# MP9929-BUCK.net
KiCad netlist of a schematic drawn in EasyEDA Pro
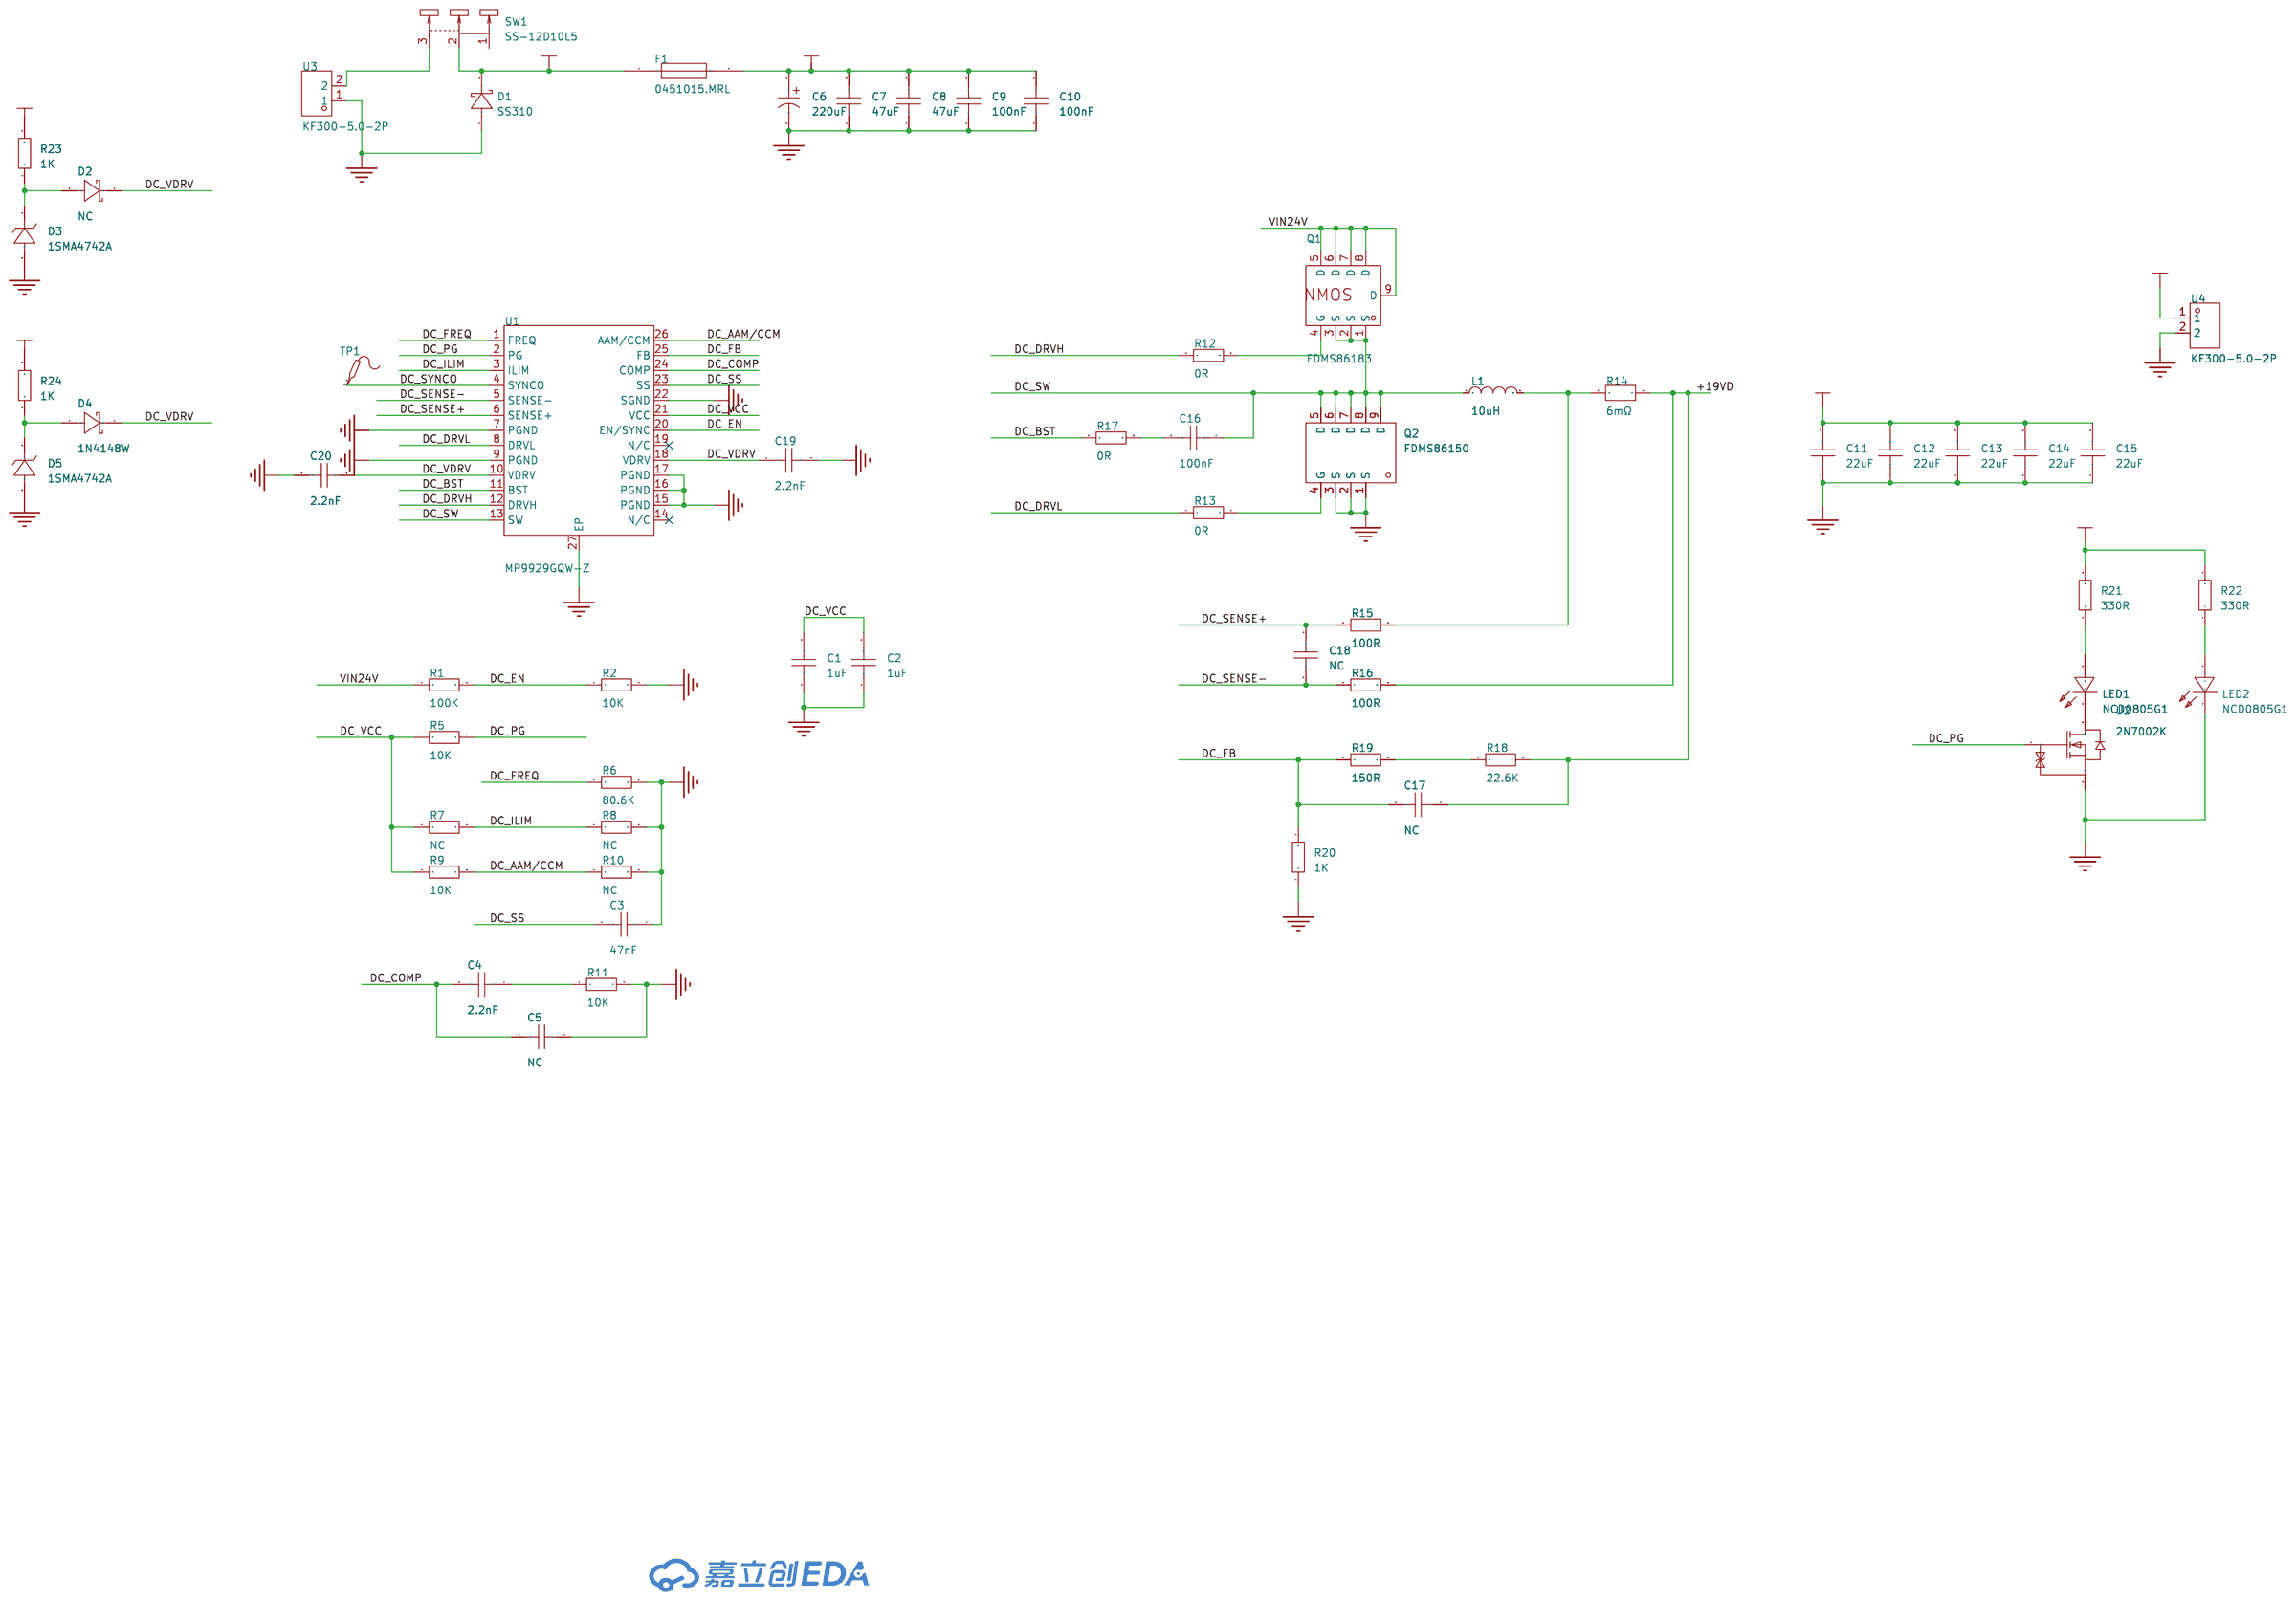
[diagram p0: schematic sheet]

(export (version "E")
  (design (tool "Eeschema 10.0.6"))
  (components
    (comp (ref "C1")
      (value "1uF")
      (footprint "easyedapro:C0603")
      (libsource (lib "easyedapro") (part "Capacitance"))
    )
    (comp (ref "C2")
      (value "1uF")
      (footprint "easyedapro:C0603")
      (libsource (lib "easyedapro") (part "Capacitance"))
    )
    (comp (ref "C3")
      (value "47nF")
      (footprint "easyedapro:C0603")
      (libsource (lib "easyedapro") (part "Capacitance"))
    )
    (comp (ref "C4")
      (value "2.2nF")
      (footprint "easyedapro:C0603")
      (libsource (lib "easyedapro") (part "Capacitance"))
    )
    (comp (ref "C5")
      (value "NC")
      (footprint "easyedapro:C0603")
      (libsource (lib "easyedapro") (part "Capacitance"))
    )
    (comp (ref "C6")
      (value "220uF")
      (footprint "easyedapro:CAP-SMD_BD10.0-L10.3-W10.3-LS11.7-FD")
      (description "容值:220uF;精度:±20%;额定电压:50V;纹波电流:220mA@120Hz;")
      (fields (field (name "Manufacturer Part") "JVJ50V220M10x10") (field (name "Manufacturer") "JIERR(捷而瑞)"))
      (libsource (lib "easyedapro") (part "JVJ50V220M10X10"))
    )
    (comp (ref "C7")
      (value "47uF")
      (footprint "easyedapro:C1210")
      (description "容值:47uF;精度:±20%;额定电压:25V;温度系数:X5R;")
      (fields
        (field (name "Manufacturer Part") "HGC1210R5476M250NSVK")
        (field (name "Manufacturer") "Chinocera(华瓷)")
      )
      (libsource (lib "easyedapro") (part "HGC1210R5476M250NSVK"))
    )
    (comp (ref "C8")
      (value "47uF")
      (footprint "easyedapro:C1210")
      (description "容值:47uF;精度:±20%;额定电压:25V;温度系数:X5R;")
      (fields
        (field (name "Manufacturer Part") "HGC1210R5476M250NSVK")
        (field (name "Manufacturer") "Chinocera(华瓷)")
      )
      (libsource (lib "easyedapro") (part "HGC1210R5476M250NSVK"))
    )
    (comp (ref "C9")
      (value "100nF")
      (footprint "easyedapro:C0603")
      (description "容值:100nF;精度:±10%;额定电压:50V;温度系数:X7R;")
      (fields
        (field (name "Manufacturer Part") "CL10B104KB8NNNC")
        (field (name "Manufacturer") "SAMSUNG(三星)")
      )
      (libsource (lib "easyedapro") (part "CL10B104KB8NNNC"))
    )
    (comp (ref "C10")
      (value "100nF")
      (footprint "easyedapro:C0603")
      (description "容值:100nF;精度:±10%;额定电压:50V;温度系数:X7R;")
      (fields
        (field (name "Manufacturer Part") "CL10B104KB8NNNC")
        (field (name "Manufacturer") "SAMSUNG(三星)")
      )
      (libsource (lib "easyedapro") (part "CL10B104KB8NNNC"))
    )
    (comp (ref "C11")
      (value "22uF")
      (footprint "easyedapro:C1210")
      (description "容值:47uF;精度:±20%;额定电压:25V;温度系数:X5R;")
      (fields
        (field (name "Manufacturer Part") "HGC1210R5476M250NSVK")
        (field (name "Manufacturer") "Chinocera(华瓷)")
      )
      (libsource (lib "easyedapro") (part "HGC1210R5476M250NSVK"))
    )
    (comp (ref "C12")
      (value "22uF")
      (footprint "easyedapro:C1210")
      (description "容值:47uF;精度:±20%;额定电压:25V;温度系数:X5R;")
      (fields
        (field (name "Manufacturer Part") "HGC1210R5476M250NSVK")
        (field (name "Manufacturer") "Chinocera(华瓷)")
      )
      (libsource (lib "easyedapro") (part "HGC1210R5476M250NSVK"))
    )
    (comp (ref "C13")
      (value "22uF")
      (footprint "easyedapro:C1210")
      (description "容值:47uF;精度:±20%;额定电压:25V;温度系数:X5R;")
      (fields
        (field (name "Manufacturer Part") "HGC1210R5476M250NSVK")
        (field (name "Manufacturer") "Chinocera(华瓷)")
      )
      (libsource (lib "easyedapro") (part "HGC1210R5476M250NSVK"))
    )
    (comp (ref "C14")
      (value "22uF")
      (footprint "easyedapro:C1210")
      (description "容值:47uF;精度:±20%;额定电压:25V;温度系数:X5R;")
      (fields
        (field (name "Manufacturer Part") "HGC1210R5476M250NSVK")
        (field (name "Manufacturer") "Chinocera(华瓷)")
      )
      (libsource (lib "easyedapro") (part "HGC1210R5476M250NSVK"))
    )
    (comp (ref "C15")
      (value "22uF")
      (footprint "easyedapro:C1210")
      (description "容值:47uF;精度:±20%;额定电压:25V;温度系数:X5R;")
      (fields
        (field (name "Manufacturer Part") "HGC1210R5476M250NSVK")
        (field (name "Manufacturer") "Chinocera(华瓷)")
      )
      (libsource (lib "easyedapro") (part "HGC1210R5476M250NSVK"))
    )
    (comp (ref "C16")
      (value "100nF")
      (footprint "easyedapro:C0603")
      (description "容值:100nF;精度:±10%;额定电压:50V;温度系数:X7R;")
      (fields
        (field (name "Manufacturer Part") "CL10B104KB8NNNC")
        (field (name "Manufacturer") "SAMSUNG(三星)")
      )
      (libsource (lib "easyedapro") (part "CL10B104KB8NNNC"))
    )
    (comp (ref "C17")
      (value "NC")
      (footprint "easyedapro:C0603")
      (libsource (lib "easyedapro") (part "Capacitance"))
    )
    (comp (ref "C18")
      (value "NC")
      (footprint "easyedapro:C0603")
      (description "容值:100nF;精度:±10%;额定电压:50V;温度系数:X7R;")
      (fields
        (field (name "Manufacturer Part") "CL10B104KB8NNNC")
        (field (name "Manufacturer") "SAMSUNG(三星)")
      )
      (libsource (lib "easyedapro") (part "CL10B104KB8NNNC"))
    )
    (comp (ref "C19")
      (value "2.2nF")
      (footprint "easyedapro:C0603")
      (libsource (lib "easyedapro") (part "Capacitance"))
    )
    (comp (ref "C20")
      (value "2.2nF")
      (footprint "easyedapro:C0603")
      (libsource (lib "easyedapro") (part "Capacitance"))
    )
    (comp (ref "D1")
      (value "SS310")
      (footprint "easyedapro:SMA_L4.3-W2.6-LS5.0-FD")
      (description "二极管配置:独立式;正向压降(Vf):850mV@3A;直流反向耐压(Vr):100V;整流电流:3A;")
      (fields (field (name "Manufacturer") "R+O(宏嘉诚)"))
      (libsource (lib "easyedapro") (part "SS310_C7420364"))
    )
    (comp (ref "D2")
      (value "NC")
      (footprint "easyedapro:SOD-123_L2.7-W1.6-LS3.7-FD")
      (description "二极管配置:独立式;正向压降(Vf):1.25V@150mA;直流反向耐压(Vr):100V;整流电流:150mA;反向恢复时间(Trr):4ns;")
      (fields (field (name "Manufacturer") "R+O(宏嘉诚)"))
      (libsource (lib "easyedapro") (part "1N4148W_C7420318"))
    )
    (comp (ref "D3")
      (value "1SMA4742A")
      (footprint "easyedapro:SMA_L4.3-W2.6-LS5.0-RD")
      (description "二极管配置:独立式;稳压值(标称值):12V;稳压值(范围):11.4V~12.6V;耗散功率(Pd):1W;")
      (fields (field (name "Manufacturer") "R+O(宏嘉诚)"))
      (libsource (lib "easyedapro") (part "1SMA4742A_C19077480"))
    )
    (comp (ref "D4")
      (value "1N4148W")
      (footprint "easyedapro:SOD-123_L2.7-W1.6-LS3.7-FD")
      (description "二极管配置:独立式;正向压降(Vf):1.25V@150mA;直流反向耐压(Vr):100V;整流电流:150mA;反向恢复时间(Trr):4ns;")
      (fields (field (name "Manufacturer") "R+O(宏嘉诚)"))
      (libsource (lib "easyedapro") (part "1N4148W_C7420318"))
    )
    (comp (ref "D5")
      (value "1SMA4742A")
      (footprint "easyedapro:SMA_L4.3-W2.6-LS5.0-RD")
      (description "二极管配置:独立式;稳压值(标称值):12V;稳压值(范围):11.4V~12.6V;耗散功率(Pd):1W;")
      (fields (field (name "Manufacturer") "R+O(宏嘉诚)"))
      (libsource (lib "easyedapro") (part "1SMA4742A_C19077480"))
    )
    (comp (ref "F1")
      (value "0451015.MRL")
      (footprint "easyedapro:FUSE-SMD_L6.1-W2.6")
      (description "类型:贴片式保险丝;额定电流:15A;额定电压 (AC):65V;额定电压:65V;分断能力:50A;")
      (fields (field (name "Manufacturer") "Littelfuse(美国力特)"))
      (libsource (lib "easyedapro") (part "0451015.MRL"))
    )
    (comp (ref "L1")
      (value "10uH")
      (footprint "easyedapro:IND-SMD_L11.5-W10.0_FXL1040")
      (description "电感值:10uH;精度:±20%;额定电流:7.8A;饱和电流(Isat):8.5A;类型:一体成型电感;")
      (fields (field (name "Manufacturer Part") "FXL1040-100-M") (field (name "Manufacturer") "cjiang(长江微电)"))
      (libsource (lib "easyedapro") (part "FXL1040-100-M"))
    )
    (comp (ref "LED1")
      (value "NCD0805G1")
      (footprint "easyedapro:LED0805-R-RD")
      (fields (field (name "Manufacturer") "国星光电"))
      (libsource (lib "easyedapro") (part "FC-2012UGK-520D5"))
    )
    (comp (ref "LED2")
      (value "NCD0805G1")
      (footprint "easyedapro:LED0805-R-RD")
      (fields (field (name "Manufacturer") "国星光电"))
      (libsource (lib "easyedapro") (part "FC-2012UGK-520D5"))
    )
    (comp (ref "Q1")
      (value "FDMS86183")
      (footprint "easyedapro:POWER-56_L5.0-W6.0-P1.27-LS6.2-BL")
      (description "类型:-;漏源电压(Vdss):-;连续漏极电流(Id):-;功率(Pd):-;导通电阻(RDS(on)@Vgs,Id):-;阈值电压(Vgs(th)@Id):-;")
      (fields (field (name "Manufacturer") "onsemi(安森美)"))
      (libsource (lib "easyedapro") (part "FDMS86183"))
    )
    (comp (ref "Q2")
      (value "FDMS86150")
      (footprint "easyedapro:POWER-56_L5.0-W6.0-P1.27-LS6.2-BL")
      (description "数量:1个N沟道;漏源电压(Vdss):100V;连续漏极电流(Id):80A;导通电阻(RDS(on)):7.8mΩ@6V,13A;耗散功率(Pd):156W;阈值电压(Vgs(th)):2V;")
      (fields (field (name "Manufacturer") "onsemi(安森美)"))
      (libsource (lib "easyedapro") (part "FDMS86150"))
    )
    (comp (ref "R1") (value "100K") (footprint "easyedapro:R0603") (libsource (lib "easyedapro") (part "电阻")))
    (comp (ref "R2") (value "10K") (footprint "easyedapro:R0603") (libsource (lib "easyedapro") (part "电阻")))
    (comp (ref "R5") (value "10K") (footprint "easyedapro:R0603") (libsource (lib "easyedapro") (part "电阻")))
    (comp (ref "R6")
      (value "80.6K")
      (footprint "easyedapro:R0603")
      (libsource (lib "easyedapro") (part "电阻"))
    )
    (comp (ref "R7") (value "NC") (footprint "easyedapro:R0603") (libsource (lib "easyedapro") (part "电阻")))
    (comp (ref "R8") (value "NC") (footprint "easyedapro:R0603") (libsource (lib "easyedapro") (part "电阻")))
    (comp (ref "R9") (value "10K") (footprint "easyedapro:R0603") (libsource (lib "easyedapro") (part "电阻")))
    (comp (ref "R10") (value "NC") (footprint "easyedapro:R0603") (libsource (lib "easyedapro") (part "电阻")))
    (comp (ref "R11") (value "10K") (footprint "easyedapro:R0603") (libsource (lib "easyedapro") (part "电阻")))
    (comp (ref "R12") (value "0R") (footprint "easyedapro:R0603") (libsource (lib "easyedapro") (part "电阻")))
    (comp (ref "R13") (value "0R") (footprint "easyedapro:R0603") (libsource (lib "easyedapro") (part "电阻")))
    (comp (ref "R14")
      (value "6mΩ")
      (footprint "easyedapro:RES-SMD_L6.4-W3.2-R2512")
      (description "电阻类型:采样电阻；合金电阻;阻值:6mΩ;精度:±1%;功率:3W;温度系数:±100ppm/°C;")
      (fields (field (name "Manufacturer Part") "RE2512F3R006") (field (name "Manufacturer") "JIERR(捷而瑞)"))
      (libsource (lib "easyedapro") (part "RE2512F3R006"))
    )
    (comp (ref "R15")
      (value "100R")
      (footprint "easyedapro:R0603")
      (libsource (lib "easyedapro") (part "电阻"))
    )
    (comp (ref "R16")
      (value "100R")
      (footprint "easyedapro:R0603")
      (libsource (lib "easyedapro") (part "电阻"))
    )
    (comp (ref "R17") (value "0R") (footprint "easyedapro:R0603") (libsource (lib "easyedapro") (part "电阻")))
    (comp (ref "R18")
      (value "22.6K")
      (footprint "easyedapro:R0603")
      (libsource (lib "easyedapro") (part "电阻"))
    )
    (comp (ref "R19")
      (value "150R")
      (footprint "easyedapro:R0603")
      (libsource (lib "easyedapro") (part "电阻"))
    )
    (comp (ref "R20") (value "1K") (footprint "easyedapro:R0603") (libsource (lib "easyedapro") (part "电阻")))
    (comp (ref "R21")
      (value "330R")
      (footprint "easyedapro:R0603")
      (libsource (lib "easyedapro") (part "电阻"))
    )
    (comp (ref "R22")
      (value "330R")
      (footprint "easyedapro:R0603")
      (libsource (lib "easyedapro") (part "电阻"))
    )
    (comp (ref "R23") (value "1K") (footprint "easyedapro:R0603") (libsource (lib "easyedapro") (part "电阻")))
    (comp (ref "R24") (value "1K") (footprint "easyedapro:R0603") (libsource (lib "easyedapro") (part "电阻")))
    (comp (ref "SW1")
      (value "SS-12D10L5")
      (footprint "easyedapro:SW-TH_SS-12D10L5")
      (description "电路结构:单刀双掷;安装方式:直插;开关颜色:黑色;额定电流:3A;额定电压:125V;工作寿命:1万次;")
      (fields (field (name "Manufacturer") "XKB Connection(中国星坤)"))
      (libsource (lib "easyedapro") (part "SS-12D10L5"))
    )
    (comp (ref "TP1")
      (value "~")
      (footprint "easyedapro:Test-Point-0.5mm")
      (description "Test Point 测试点")
      (libsource (lib "easyedapro") (part "Test-Point"))
    )
    (comp (ref "U1")
      (value "MP9929GQW-Z")
      (footprint "easyedapro:QFN-26_L6.0-W4.0-P0.50_MP9929GQW-Z")
      (fields (field (name "Manufacturer") "MPS(芯源)"))
      (libsource (lib "easyedapro") (part "MP9929GQW-Z"))
    )
    (comp (ref "U2")
      (value "2N7002K")
      (footprint "easyedapro:SOT-23-3_L2.9-W1.3-P0.95-LS2.4-BR")
      (fields (field (name "Manufacturer") "R+O(宏嘉诚)"))
      (libsource (lib "easyedapro") (part "2N7002K_C22379475"))
    )
    (comp (ref "U3")
      (value "KF300-5.0-2P")
      (footprint "easyedapro:CONN-TH_P5.00_KF300-5.0-2P")
      (fields (field (name "Manufacturer") "KEFA(科发)"))
      (libsource (lib "easyedapro") (part "KF300-5.0-2P"))
    )
    (comp (ref "U4")
      (value "KF300-5.0-2P")
      (footprint "easyedapro:CONN-TH_P5.00_KF300-5.0-2P")
      (fields (field (name "Manufacturer") "KEFA(科发)"))
      (libsource (lib "easyedapro") (part "KF300-5.0-2P"))
    )
  )
  (nets
    (net (code "1") (name "+19VD") (class "Default")
      (node (ref "C11") (pin "2") (pinfunction "2_2") (pintype "unspecified"))
      (node (ref "C12") (pin "2") (pinfunction "2_2") (pintype "unspecified"))
      (node (ref "C13") (pin "2") (pinfunction "2_2") (pintype "unspecified"))
      (node (ref "C14") (pin "2") (pinfunction "2_2") (pintype "unspecified"))
      (node (ref "C15") (pin "2") (pinfunction "2_2") (pintype "unspecified"))
      (node (ref "C17") (pin "1") (pinfunction "1_1") (pintype "input"))
      (node (ref "R14") (pin "2") (pinfunction "2_2") (pintype "unspecified"))
      (node (ref "R16") (pin "2") (pinfunction "2_2") (pintype "input"))
      (node (ref "R18") (pin "2") (pinfunction "2_2") (pintype "input"))
      (node (ref "R21") (pin "2") (pinfunction "2_2") (pintype "input"))
      (node (ref "R22") (pin "2") (pinfunction "2_2") (pintype "input"))
      (node (ref "R23") (pin "2") (pinfunction "2_2") (pintype "input"))
      (node (ref "U4") (pin "1") (pinfunction "1_1") (pintype "unspecified"))
    )
    (net (code "2") (name "/DC_AAM{slash}CCM") (class "Default")
      (node (ref "R10") (pin "1") (pinfunction "1_1") (pintype "input"))
      (node (ref "R9") (pin "2") (pinfunction "2_2") (pintype "input"))
      (node (ref "U1") (pin "26") (pinfunction "AAM/CCM_26") (pintype "unspecified"))
    )
    (net (code "3") (name "/DC_BST") (class "Default")
      (node (ref "R17") (pin "1") (pinfunction "1_1") (pintype "input"))
      (node (ref "U1") (pin "11") (pinfunction "BST_11") (pintype "unspecified"))
    )
    (net (code "4") (name "/DC_COMP") (class "Default")
      (node (ref "C4") (pin "2") (pinfunction "2_2") (pintype "input"))
      (node (ref "C5") (pin "2") (pinfunction "2_2") (pintype "input"))
      (node (ref "U1") (pin "24") (pinfunction "COMP_24") (pintype "unspecified"))
    )
    (net (code "5") (name "/DC_DRVH") (class "Default")
      (node (ref "R12") (pin "1") (pinfunction "1_1") (pintype "input"))
      (node (ref "U1") (pin "12") (pinfunction "DRVH_12") (pintype "unspecified"))
    )
    (net (code "6") (name "/DC_DRVL") (class "Default")
      (node (ref "R13") (pin "1") (pinfunction "1_1") (pintype "input"))
      (node (ref "U1") (pin "8") (pinfunction "DRVL_8") (pintype "unspecified"))
    )
    (net (code "7") (name "/DC_EN") (class "Default")
      (node (ref "R1") (pin "2") (pinfunction "2_2") (pintype "input"))
      (node (ref "R2") (pin "1") (pinfunction "1_1") (pintype "input"))
      (node (ref "U1") (pin "20") (pinfunction "EN/SYNC_20") (pintype "unspecified"))
    )
    (net (code "8") (name "/DC_FB") (class "Default")
      (node (ref "C17") (pin "2") (pinfunction "2_2") (pintype "input"))
      (node (ref "R19") (pin "1") (pinfunction "1_1") (pintype "input"))
      (node (ref "R20") (pin "2") (pinfunction "2_2") (pintype "input"))
      (node (ref "U1") (pin "25") (pinfunction "FB_25") (pintype "unspecified"))
    )
    (net (code "9") (name "/DC_FREQ") (class "Default")
      (node (ref "R6") (pin "1") (pinfunction "1_1") (pintype "input"))
      (node (ref "U1") (pin "1") (pinfunction "FREQ_1") (pintype "unspecified"))
    )
    (net (code "10") (name "/DC_ILIM") (class "Default")
      (node (ref "R7") (pin "2") (pinfunction "2_2") (pintype "input"))
      (node (ref "R8") (pin "1") (pinfunction "1_1") (pintype "input"))
      (node (ref "U1") (pin "3") (pinfunction "ILIM_3") (pintype "unspecified"))
    )
    (net (code "11") (name "/DC_PG") (class "Default")
      (node (ref "R5") (pin "2") (pinfunction "2_2") (pintype "input"))
      (node (ref "U1") (pin "2") (pinfunction "PG_2") (pintype "unspecified"))
      (node (ref "U2") (pin "1") (pinfunction "G_1") (pintype "unspecified"))
    )
    (net (code "12") (name "/DC_SENSE+") (class "Default")
      (node (ref "C18") (pin "1") (pinfunction "1_1") (pintype "unspecified"))
      (node (ref "R15") (pin "1") (pinfunction "1_1") (pintype "input"))
      (node (ref "U1") (pin "6") (pinfunction "SENSE+_6") (pintype "unspecified"))
    )
    (net (code "13") (name "/DC_SENSE-") (class "Default")
      (node (ref "C18") (pin "2") (pinfunction "2_2") (pintype "unspecified"))
      (node (ref "R16") (pin "1") (pinfunction "1_1") (pintype "input"))
      (node (ref "U1") (pin "5") (pinfunction "SENSE-_5") (pintype "unspecified"))
    )
    (net (code "14") (name "/DC_SS") (class "Default")
      (node (ref "C3") (pin "2") (pinfunction "2_2") (pintype "input"))
      (node (ref "U1") (pin "23") (pinfunction "SS_23") (pintype "unspecified"))
    )
    (net (code "15") (name "/DC_SW") (class "Default")
      (node (ref "C16") (pin "1") (pinfunction "1_1") (pintype "unspecified"))
      (node (ref "L1") (pin "1") (pinfunction "1_1") (pintype "unspecified"))
      (node (ref "Q1") (pin "1") (pinfunction "S_1") (pintype "unspecified"))
      (node (ref "Q1") (pin "2") (pinfunction "S_2") (pintype "unspecified"))
      (node (ref "Q1") (pin "3") (pinfunction "S_3") (pintype "unspecified"))
      (node (ref "Q2") (pin "5") (pinfunction "D_5") (pintype "unspecified"))
      (node (ref "Q2") (pin "6") (pinfunction "D_6") (pintype "unspecified"))
      (node (ref "Q2") (pin "7") (pinfunction "D_7") (pintype "unspecified"))
      (node (ref "Q2") (pin "8") (pinfunction "D_8") (pintype "unspecified"))
      (node (ref "Q2") (pin "9") (pinfunction "D_9") (pintype "unspecified"))
      (node (ref "U1") (pin "13") (pinfunction "SW_13") (pintype "unspecified"))
    )
    (net (code "16") (name "/DC_SYNCO") (class "Default")
      (node (ref "TP1") (pin "1") (pinfunction "1_1") (pintype "input"))
      (node (ref "U1") (pin "4") (pinfunction "SYNCO_4") (pintype "unspecified"))
    )
    (net (code "17") (name "/DC_VCC") (class "Default")
      (node (ref "C1") (pin "2") (pinfunction "2_2") (pintype "input"))
      (node (ref "C2") (pin "2") (pinfunction "2_2") (pintype "input"))
      (node (ref "R5") (pin "1") (pinfunction "1_1") (pintype "input"))
      (node (ref "R7") (pin "1") (pinfunction "1_1") (pintype "input"))
      (node (ref "R9") (pin "1") (pinfunction "1_1") (pintype "input"))
      (node (ref "U1") (pin "21") (pinfunction "VCC_21") (pintype "unspecified"))
    )
    (net (code "18") (name "/DC_VDRV") (class "Default")
      (node (ref "C19") (pin "1") (pinfunction "1_1") (pintype "input"))
      (node (ref "C20") (pin "2") (pinfunction "2_2") (pintype "input"))
      (node (ref "D2") (pin "2") (pinfunction "K_2") (pintype "unspecified"))
      (node (ref "D4") (pin "2") (pinfunction "K_2") (pintype "unspecified"))
      (node (ref "U1") (pin "10") (pinfunction "VDRV_10") (pintype "unspecified"))
      (node (ref "U1") (pin "18") (pinfunction "VDRV_18") (pintype "unspecified"))
    )
    (net (code "19") (name "GND") (class "Default")
      (node (ref "C1") (pin "1") (pinfunction "1_1") (pintype "input"))
      (node (ref "C10") (pin "1") (pinfunction "1_1") (pintype "unspecified"))
      (node (ref "C11") (pin "1") (pinfunction "1_1") (pintype "unspecified"))
      (node (ref "C12") (pin "1") (pinfunction "1_1") (pintype "unspecified"))
      (node (ref "C13") (pin "1") (pinfunction "1_1") (pintype "unspecified"))
      (node (ref "C14") (pin "1") (pinfunction "1_1") (pintype "unspecified"))
      (node (ref "C15") (pin "1") (pinfunction "1_1") (pintype "unspecified"))
      (node (ref "C19") (pin "2") (pinfunction "2_2") (pintype "input"))
      (node (ref "C2") (pin "1") (pinfunction "1_1") (pintype "input"))
      (node (ref "C20") (pin "1") (pinfunction "1_1") (pintype "input"))
      (node (ref "C3") (pin "1") (pinfunction "1_1") (pintype "input"))
      (node (ref "C5") (pin "1") (pinfunction "1_1") (pintype "input"))
      (node (ref "C6") (pin "2") (pinfunction "2_2") (pintype "input"))
      (node (ref "C7") (pin "1") (pinfunction "1_1") (pintype "unspecified"))
      (node (ref "C8") (pin "1") (pinfunction "1_1") (pintype "unspecified"))
      (node (ref "C9") (pin "1") (pinfunction "1_1") (pintype "unspecified"))
      (node (ref "D1") (pin "1") (pinfunction "A_1") (pintype "unspecified"))
      (node (ref "D3") (pin "2") (pinfunction "A_2") (pintype "unspecified"))
      (node (ref "D5") (pin "2") (pinfunction "A_2") (pintype "unspecified"))
      (node (ref "LED2") (pin "2") (pinfunction "K_2") (pintype "unspecified"))
      (node (ref "Q2") (pin "1") (pinfunction "S_1") (pintype "unspecified"))
      (node (ref "Q2") (pin "2") (pinfunction "S_2") (pintype "unspecified"))
      (node (ref "Q2") (pin "3") (pinfunction "S_3") (pintype "unspecified"))
      (node (ref "R10") (pin "2") (pinfunction "2_2") (pintype "input"))
      (node (ref "R11") (pin "2") (pinfunction "2_2") (pintype "input"))
      (node (ref "R2") (pin "2") (pinfunction "2_2") (pintype "input"))
      (node (ref "R20") (pin "1") (pinfunction "1_1") (pintype "input"))
      (node (ref "R6") (pin "2") (pinfunction "2_2") (pintype "input"))
      (node (ref "R8") (pin "2") (pinfunction "2_2") (pintype "input"))
      (node (ref "U1") (pin "15") (pinfunction "PGND_15") (pintype "unspecified"))
      (node (ref "U1") (pin "16") (pinfunction "PGND_16") (pintype "unspecified"))
      (node (ref "U1") (pin "17") (pinfunction "PGND_17") (pintype "unspecified"))
      (node (ref "U1") (pin "22") (pinfunction "SGND_22") (pintype "unspecified"))
      (node (ref "U1") (pin "27") (pinfunction "EP_27") (pintype "unspecified"))
      (node (ref "U1") (pin "7") (pinfunction "PGND_7") (pintype "unspecified"))
      (node (ref "U1") (pin "9") (pinfunction "PGND_9") (pintype "unspecified"))
      (node (ref "U2") (pin "2") (pinfunction "S_2") (pintype "unspecified"))
      (node (ref "U3") (pin "1") (pinfunction "1_1") (pintype "unspecified"))
      (node (ref "U4") (pin "2") (pinfunction "2_2") (pintype "unspecified"))
    )
    (net (code "20") (name "Net-(C4-Pad1)") (class "Default")
      (node (ref "C4") (pin "1") (pinfunction "1_1") (pintype "input"))
      (node (ref "R11") (pin "1") (pinfunction "1_1") (pintype "input"))
    )
    (net (code "21") (name "Net-(C16-Pad2)") (class "Default")
      (node (ref "C16") (pin "2") (pinfunction "2_2") (pintype "unspecified"))
      (node (ref "R17") (pin "2") (pinfunction "2_2") (pintype "input"))
    )
    (net (code "22") (name "Net-(D2-A)") (class "Default")
      (node (ref "D2") (pin "1") (pinfunction "A_1") (pintype "unspecified"))
      (node (ref "D3") (pin "1") (pinfunction "K_1") (pintype "unspecified"))
      (node (ref "R23") (pin "1") (pinfunction "1_1") (pintype "input"))
    )
    (net (code "23") (name "Net-(D4-A)") (class "Default")
      (node (ref "D4") (pin "1") (pinfunction "A_1") (pintype "unspecified"))
      (node (ref "D5") (pin "1") (pinfunction "K_1") (pintype "unspecified"))
      (node (ref "R24") (pin "1") (pinfunction "1_1") (pintype "input"))
    )
    (net (code "24") (name "Net-(L1-Pad2)") (class "Default")
      (node (ref "L1") (pin "2") (pinfunction "2_2") (pintype "unspecified"))
      (node (ref "R14") (pin "1") (pinfunction "1_1") (pintype "unspecified"))
      (node (ref "R15") (pin "2") (pinfunction "2_2") (pintype "input"))
    )
    (net (code "25") (name "Net-(LED1-A)") (class "Default")
      (node (ref "LED1") (pin "1") (pinfunction "A_1") (pintype "unspecified"))
      (node (ref "R21") (pin "1") (pinfunction "1_1") (pintype "input"))
    )
    (net (code "26") (name "Net-(LED1-K)") (class "Default")
      (node (ref "LED1") (pin "2") (pinfunction "K_2") (pintype "unspecified"))
      (node (ref "U2") (pin "3") (pinfunction "D_3") (pintype "unspecified"))
    )
    (net (code "27") (name "Net-(LED2-A)") (class "Default")
      (node (ref "LED2") (pin "1") (pinfunction "A_1") (pintype "unspecified"))
      (node (ref "R22") (pin "1") (pinfunction "1_1") (pintype "input"))
    )
    (net (code "28") (name "Net-(Q1-G)") (class "Default")
      (node (ref "Q1") (pin "4") (pinfunction "G_4") (pintype "unspecified"))
      (node (ref "R12") (pin "2") (pinfunction "2_2") (pintype "input"))
    )
    (net (code "29") (name "Net-(Q2-G)") (class "Default")
      (node (ref "Q2") (pin "4") (pinfunction "G_4") (pintype "unspecified"))
      (node (ref "R13") (pin "2") (pinfunction "2_2") (pintype "input"))
    )
    (net (code "30") (name "Net-(R18-Pad1)") (class "Default")
      (node (ref "R18") (pin "1") (pinfunction "1_1") (pintype "input"))
      (node (ref "R19") (pin "2") (pinfunction "2_2") (pintype "input"))
    )
    (net (code "31") (name "Net-(SW1-Pad3)") (class "Default")
      (node (ref "SW1") (pin "3") (pinfunction "3_3") (pintype "unspecified"))
      (node (ref "U3") (pin "2") (pinfunction "2_2") (pintype "unspecified"))
    )
    (net (code "32") (name "VIN") (class "Default")
      (node (ref "D1") (pin "2") (pinfunction "K_2") (pintype "unspecified"))
      (node (ref "F1") (pin "1") (pinfunction "1_1") (pintype "unspecified"))
      (node (ref "SW1") (pin "2") (pinfunction "2_2") (pintype "unspecified"))
    )
    (net (code "33") (name "VIN24V") (class "Default")
      (node (ref "C10") (pin "2") (pinfunction "2_2") (pintype "unspecified"))
      (node (ref "C6") (pin "1") (pinfunction "1_1") (pintype "input"))
      (node (ref "C7") (pin "2") (pinfunction "2_2") (pintype "unspecified"))
      (node (ref "C8") (pin "2") (pinfunction "2_2") (pintype "unspecified"))
      (node (ref "C9") (pin "2") (pinfunction "2_2") (pintype "unspecified"))
      (node (ref "F1") (pin "2") (pinfunction "2_2") (pintype "unspecified"))
      (node (ref "Q1") (pin "5") (pinfunction "D_5") (pintype "unspecified"))
      (node (ref "Q1") (pin "6") (pinfunction "D_6") (pintype "unspecified"))
      (node (ref "Q1") (pin "7") (pinfunction "D_7") (pintype "unspecified"))
      (node (ref "Q1") (pin "8") (pinfunction "D_8") (pintype "unspecified"))
      (node (ref "Q1") (pin "9") (pinfunction "D_9") (pintype "unspecified"))
      (node (ref "R1") (pin "1") (pinfunction "1_1") (pintype "input"))
      (node (ref "R24") (pin "2") (pinfunction "2_2") (pintype "input"))
    )
    (net (code "34") (name "unconnected-(SW1-Pad1)") (class "Default")
      (node (ref "SW1") (pin "1") (pinfunction "1_1") (pintype "unspecified"))
    )
    (net (code "35") (name "unconnected-(U1-N{slash}C-Pad14)") (class "Default")
      (node (ref "U1") (pin "14") (pinfunction "N/C_14") (pintype "unspecified+no_connect"))
    )
    (net (code "36") (name "unconnected-(U1-N{slash}C-Pad19)") (class "Default")
      (node (ref "U1") (pin "19") (pinfunction "N/C_19") (pintype "unspecified+no_connect"))
    )
  )
)
